# 780-00012-P1_Sch_M2_Focus_Drive.net
KiCad netlist of a schematic drawn in Altium Designer
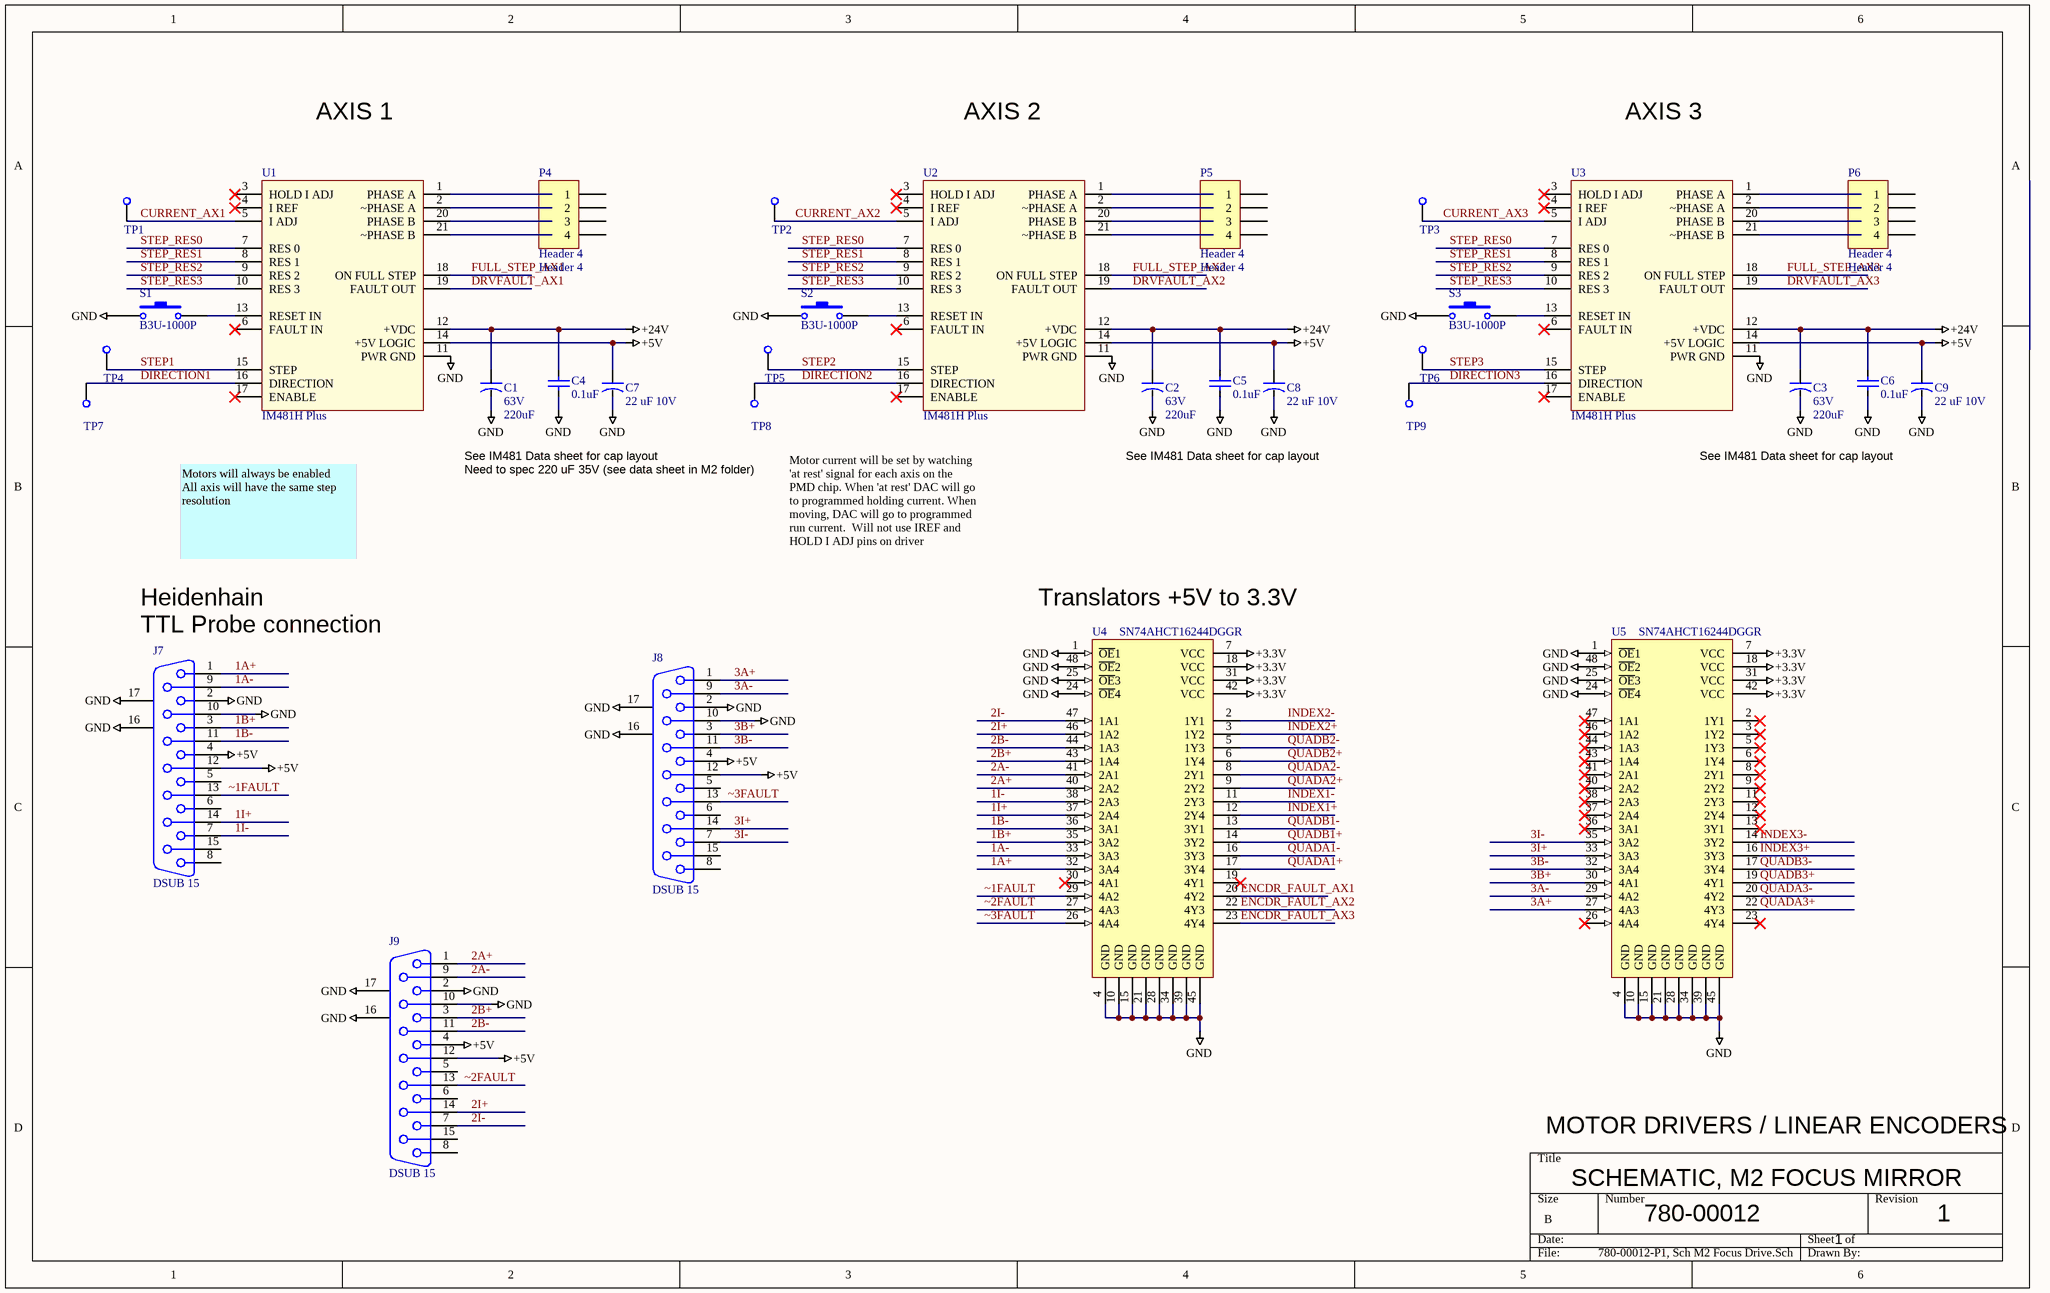
[diagram p0: 780-00012-P1, Sch M2 Focus Drive.SchDoc]

(export (version "E")
  (design (tool "Eeschema 10.0.6"))
  (components
    (comp (ref "C1")
      (value "63V")
      (footprint "CAP 220uF 63V")
      (description "CAP 220UF 63V ELECT MVH SMD")
      (fields (field (name "MANUFACTURER") "United Chemi-Con") (field (name "ALTIUM_VALUE") "220uF"))
      (libsource (lib "Richs Schematic Components") (part "Cap 220uF, 63V"))
    )
    (comp (ref "C2")
      (value "63V")
      (footprint "CAP 220uF 63V")
      (description "CAP 220UF 63V ELECT MVH SMD")
      (fields (field (name "MANUFACTURER") "United Chemi-Con") (field (name "ALTIUM_VALUE") "220uF"))
      (libsource (lib "Richs Schematic Components") (part "Cap 220uF, 63V"))
    )
    (comp (ref "C3")
      (value "63V")
      (footprint "CAP 220uF 63V")
      (description "CAP 220UF 63V ELECT MVH SMD")
      (fields (field (name "MANUFACTURER") "United Chemi-Con") (field (name "ALTIUM_VALUE") "220uF"))
      (libsource (lib "Richs Schematic Components") (part "Cap 220uF, 63V"))
    )
    (comp (ref "C4")
      (value "0.1uF")
      (footprint "SMD_0805")
      (description "Capacitor")
      (fields (field (name "Comment") "Cap SMD"))
      (libsource (lib "Richs Schematic Components") (part "Cap SMD"))
    )
    (comp (ref "C5")
      (value "0.1uF")
      (footprint "SMD_0805")
      (description "Capacitor")
      (fields (field (name "Comment") "Cap SMD"))
      (libsource (lib "Richs Schematic Components") (part "Cap SMD"))
    )
    (comp (ref "C6")
      (value "0.1uF")
      (footprint "SMD_0805")
      (description "Capacitor")
      (fields (field (name "Comment") "Cap SMD"))
      (libsource (lib "Richs Schematic Components") (part "Cap SMD"))
    )
    (comp (ref "C7")
      (value "22 uF 10V")
      (footprint "SMD_CAP_3216")
      (description "outline 3.2mm x 1.6mm")
      (fields (field (name "MANUFACTURER") "KEMET") (field (name "Comment") "16V"))
      (libsource (lib "Richs Schematic Components") (part "Cap Tant 16V"))
    )
    (comp (ref "C8")
      (value "22 uF 10V")
      (footprint "SMD_CAP_3216")
      (description "outline 3.2mm x 1.6mm")
      (fields (field (name "MANUFACTURER") "KEMET") (field (name "Comment") "16V"))
      (libsource (lib "Richs Schematic Components") (part "Cap Tant 16V"))
    )
    (comp (ref "C9")
      (value "22 uF 10V")
      (footprint "SMD_CAP_3216")
      (description "outline 3.2mm x 1.6mm")
      (fields (field (name "MANUFACTURER") "KEMET") (field (name "Comment") "16V"))
      (libsource (lib "Richs Schematic Components") (part "Cap Tant 16V"))
    )
    (comp (ref "J7")
      (value "DSUB 15")
      (footprint "DSUB15 PCB VERT Female")
      (description "Receptacle Assembly, 15 Position")
      (libsource (lib "Richs Schematic Components") (part "DSUB 15"))
    )
    (comp (ref "J8")
      (value "DSUB 15")
      (footprint "DSUB15 PCB VERT Female")
      (description "Receptacle Assembly, 15 Position")
      (libsource (lib "Richs Schematic Components") (part "DSUB 15"))
    )
    (comp (ref "J9")
      (value "DSUB 15")
      (footprint "DSUB15 PCB VERT Female")
      (description "Receptacle Assembly, 15 Position")
      (libsource (lib "Richs Schematic Components") (part "DSUB 15"))
    )
    (comp (ref "P4")
      (value "Header 4")
      (footprint "HDR1X4 for IDC")
      (description "Header, 4-Pin")
      (fields (field (name "ALTIUM_VALUE") "Header 4"))
      (libsource (lib "Richs Schematic Components") (part "Header 4"))
    )
    (comp (ref "P5")
      (value "Header 4")
      (footprint "HDR1X4 for IDC")
      (description "Header, 4-Pin")
      (fields (field (name "ALTIUM_VALUE") "Header 4"))
      (libsource (lib "Richs Schematic Components") (part "Header 4"))
    )
    (comp (ref "P6")
      (value "Header 4")
      (footprint "HDR1X4 for IDC")
      (description "Header, 4-Pin")
      (fields (field (name "ALTIUM_VALUE") "Header 4"))
      (libsource (lib "Richs Schematic Components") (part "Header 4"))
    )
    (comp (ref "S1")
      (value "B3U-1000P")
      (footprint "B3U-1000P")
      (description "Switch")
      (fields (field (name "MANUFACTURER") "Omron Electronics"))
      (libsource (lib "Miscellaneous Devices") (part "SW-PB"))
    )
    (comp (ref "S2")
      (value "B3U-1000P")
      (footprint "B3U-1000P")
      (description "Switch")
      (fields (field (name "MANUFACTURER") "Omron Electronics"))
      (libsource (lib "Miscellaneous Devices") (part "SW-PB"))
    )
    (comp (ref "S3")
      (value "B3U-1000P")
      (footprint "B3U-1000P")
      (description "Switch")
      (fields (field (name "MANUFACTURER") "Omron Electronics"))
      (libsource (lib "Miscellaneous Devices") (part "SW-PB"))
    )
    (comp (ref "TP1")
      (value "Test Point SMD")
      (footprint "SMD_TEST POINT")
      (description "SMD loop test point")
      (libsource (lib "Richs Schematic Components") (part "Test Point SMD"))
    )
    (comp (ref "TP2")
      (value "Test Point SMD")
      (footprint "SMD_TEST POINT")
      (description "SMD loop test point")
      (libsource (lib "Richs Schematic Components") (part "Test Point SMD"))
    )
    (comp (ref "TP3")
      (value "Test Point SMD")
      (footprint "SMD_TEST POINT")
      (description "SMD loop test point")
      (libsource (lib "Richs Schematic Components") (part "Test Point SMD"))
    )
    (comp (ref "TP4")
      (value "Test Point SMD")
      (footprint "SMD_TEST POINT")
      (description "SMD loop test point")
      (libsource (lib "Richs Schematic Components") (part "Test Point SMD"))
    )
    (comp (ref "TP5")
      (value "Test Point SMD")
      (footprint "SMD_TEST POINT")
      (description "SMD loop test point")
      (libsource (lib "Richs Schematic Components") (part "Test Point SMD"))
    )
    (comp (ref "TP6")
      (value "Test Point SMD")
      (footprint "SMD_TEST POINT")
      (description "SMD loop test point")
      (libsource (lib "Richs Schematic Components") (part "Test Point SMD"))
    )
    (comp (ref "TP7")
      (value "Test Point SMD")
      (footprint "SMD_TEST POINT")
      (description "SMD loop test point")
      (libsource (lib "Richs Schematic Components") (part "Test Point SMD"))
    )
    (comp (ref "TP8")
      (value "Test Point SMD")
      (footprint "SMD_TEST POINT")
      (description "SMD loop test point")
      (libsource (lib "Richs Schematic Components") (part "Test Point SMD"))
    )
    (comp (ref "TP9")
      (value "Test Point SMD")
      (footprint "SMD_TEST POINT")
      (description "SMD loop test point")
      (libsource (lib "Richs Schematic Components") (part "Test Point SMD"))
    )
    (comp (ref "U1")
      (value "IM481H Plus")
      (footprint "IM481H Vertical")
      (description "Hybrid stepper motor driver")
      (libsource (lib "Richs Schematic Components") (part "IM481H Plus"))
    )
    (comp (ref "U2")
      (value "IM481H Plus")
      (footprint "IM481H Vertical")
      (description "Hybrid stepper motor driver")
      (libsource (lib "Richs Schematic Components") (part "IM481H Plus"))
    )
    (comp (ref "U3")
      (value "IM481H Plus")
      (footprint "IM481H Vertical")
      (description "Hybrid stepper motor driver")
      (libsource (lib "Richs Schematic Components") (part "IM481H Plus"))
    )
    (comp (ref "U4")
      (value "SN74AHCT16244DGGR")
      (footprint "DGG048_N")
      (description "16-Bit Buffer/Driver with 3-State Outputs")
      (libsource (lib "TI Logic Buffer Line Driver") (part "SN74AHCT16244DGGR"))
    )
    (comp (ref "U5")
      (value "SN74AHCT16244DGGR")
      (footprint "DGG048_N")
      (description "16-Bit Buffer/Driver with 3-State Outputs")
      (libsource (lib "TI Logic Buffer Line Driver") (part "SN74AHCT16244DGGR"))
    )
  )
  (nets
    (net (code "1") (name "+3.3V") (class "Default")
      (node (ref "U4") (pin "18") (pinfunction "VCC_18") (pintype "power_in"))
      (node (ref "U4") (pin "31") (pinfunction "VCC_31") (pintype "power_in"))
      (node (ref "U4") (pin "42") (pinfunction "VCC_42") (pintype "power_in"))
      (node (ref "U4") (pin "7") (pinfunction "VCC_7") (pintype "power_in"))
      (node (ref "U5") (pin "18") (pinfunction "VCC_18") (pintype "power_in"))
      (node (ref "U5") (pin "31") (pinfunction "VCC_31") (pintype "power_in"))
      (node (ref "U5") (pin "42") (pinfunction "VCC_42") (pintype "power_in"))
      (node (ref "U5") (pin "7") (pinfunction "VCC_7") (pintype "power_in"))
    )
    (net (code "2") (name "+5V") (class "Default")
      (node (ref "C7") (pin "1") (pinfunction "1_1") (pintype "passive"))
      (node (ref "C8") (pin "1") (pinfunction "1_1") (pintype "passive"))
      (node (ref "C9") (pin "1") (pinfunction "1_1") (pintype "passive"))
      (node (ref "J7") (pin "12") (pinfunction "12_12") (pintype "passive"))
      (node (ref "J7") (pin "4") (pinfunction "4_4") (pintype "passive"))
      (node (ref "J8") (pin "12") (pinfunction "12_12") (pintype "passive"))
      (node (ref "J8") (pin "4") (pinfunction "4_4") (pintype "passive"))
      (node (ref "J9") (pin "12") (pinfunction "12_12") (pintype "passive"))
      (node (ref "J9") (pin "4") (pinfunction "4_4") (pintype "passive"))
      (node (ref "U1") (pin "14") (pinfunction "+5V_LOGIC_14") (pintype "passive"))
      (node (ref "U2") (pin "14") (pinfunction "+5V_LOGIC_14") (pintype "passive"))
      (node (ref "U3") (pin "14") (pinfunction "+5V_LOGIC_14") (pintype "passive"))
    )
    (net (code "3") (name "+24V") (class "Default")
      (node (ref "C1") (pin "1") (pinfunction "1_1") (pintype "passive"))
      (node (ref "C2") (pin "1") (pinfunction "1_1") (pintype "passive"))
      (node (ref "C3") (pin "1") (pinfunction "1_1") (pintype "passive"))
      (node (ref "C4") (pin "2") (pinfunction "2_2") (pintype "passive"))
      (node (ref "C5") (pin "2") (pinfunction "2_2") (pintype "passive"))
      (node (ref "C6") (pin "2") (pinfunction "2_2") (pintype "passive"))
      (node (ref "U1") (pin "12") (pinfunction "+VDC_12") (pintype "passive"))
      (node (ref "U2") (pin "12") (pinfunction "+VDC_12") (pintype "passive"))
      (node (ref "U3") (pin "12") (pinfunction "+VDC_12") (pintype "passive"))
    )
    (net (code "4") (name "/1A+") (class "Default")
      (node (ref "J7") (pin "1") (pinfunction "1_1") (pintype "passive"))
      (node (ref "U4") (pin "32") (pinfunction "3A4_32") (pintype "input"))
    )
    (net (code "5") (name "/1A-") (class "Default")
      (node (ref "J7") (pin "9") (pinfunction "9_9") (pintype "passive"))
      (node (ref "U4") (pin "33") (pinfunction "3A3_33") (pintype "input"))
    )
    (net (code "6") (name "/1B+") (class "Default")
      (node (ref "J7") (pin "3") (pinfunction "3_3") (pintype "passive"))
      (node (ref "U4") (pin "35") (pinfunction "3A2_35") (pintype "input"))
    )
    (net (code "7") (name "/1B-") (class "Default")
      (node (ref "J7") (pin "11") (pinfunction "11_11") (pintype "passive"))
      (node (ref "U4") (pin "36") (pinfunction "3A1_36") (pintype "input"))
    )
    (net (code "8") (name "/1I+") (class "Default")
      (node (ref "J7") (pin "14") (pinfunction "14_14") (pintype "passive"))
      (node (ref "U4") (pin "37") (pinfunction "2A4_37") (pintype "input"))
    )
    (net (code "9") (name "/1I-") (class "Default")
      (node (ref "J7") (pin "7") (pinfunction "7_7") (pintype "passive"))
      (node (ref "U4") (pin "38") (pinfunction "2A3_38") (pintype "input"))
    )
    (net (code "10") (name "/2A+") (class "Default")
      (node (ref "J9") (pin "1") (pinfunction "1_1") (pintype "passive"))
      (node (ref "U4") (pin "40") (pinfunction "2A2_40") (pintype "input"))
    )
    (net (code "11") (name "/2A-") (class "Default")
      (node (ref "J9") (pin "9") (pinfunction "9_9") (pintype "passive"))
      (node (ref "U4") (pin "41") (pinfunction "2A1_41") (pintype "input"))
    )
    (net (code "12") (name "/2B+") (class "Default")
      (node (ref "J9") (pin "3") (pinfunction "3_3") (pintype "passive"))
      (node (ref "U4") (pin "43") (pinfunction "1A4_43") (pintype "input"))
    )
    (net (code "13") (name "/2B-") (class "Default")
      (node (ref "J9") (pin "11") (pinfunction "11_11") (pintype "passive"))
      (node (ref "U4") (pin "44") (pinfunction "1A3_44") (pintype "input"))
    )
    (net (code "14") (name "/2I+") (class "Default")
      (node (ref "J9") (pin "14") (pinfunction "14_14") (pintype "passive"))
      (node (ref "U4") (pin "46") (pinfunction "1A2_46") (pintype "input"))
    )
    (net (code "15") (name "/2I-") (class "Default")
      (node (ref "J9") (pin "7") (pinfunction "7_7") (pintype "passive"))
      (node (ref "U4") (pin "47") (pinfunction "1A1_47") (pintype "input"))
    )
    (net (code "16") (name "/3A+") (class "Default")
      (node (ref "J8") (pin "1") (pinfunction "1_1") (pintype "passive"))
      (node (ref "U5") (pin "27") (pinfunction "4A3_27") (pintype "input"))
    )
    (net (code "17") (name "/3A-") (class "Default")
      (node (ref "J8") (pin "9") (pinfunction "9_9") (pintype "passive"))
      (node (ref "U5") (pin "29") (pinfunction "4A2_29") (pintype "input"))
    )
    (net (code "18") (name "/3B+") (class "Default")
      (node (ref "J8") (pin "3") (pinfunction "3_3") (pintype "passive"))
      (node (ref "U5") (pin "30") (pinfunction "4A1_30") (pintype "input"))
    )
    (net (code "19") (name "/3B-") (class "Default")
      (node (ref "J8") (pin "11") (pinfunction "11_11") (pintype "passive"))
      (node (ref "U5") (pin "32") (pinfunction "3A4_32") (pintype "input"))
    )
    (net (code "20") (name "/3I+") (class "Default")
      (node (ref "J8") (pin "14") (pinfunction "14_14") (pintype "passive"))
      (node (ref "U5") (pin "33") (pinfunction "3A3_33") (pintype "input"))
    )
    (net (code "21") (name "/3I-") (class "Default")
      (node (ref "J8") (pin "7") (pinfunction "7_7") (pintype "passive"))
      (node (ref "U5") (pin "35") (pinfunction "3A2_35") (pintype "input"))
    )
    (net (code "22") (name "/CURRENT_AX1") (class "Default")
      (node (ref "TP1") (pin "1") (pinfunction "TP_1") (pintype "passive"))
      (node (ref "U1") (pin "5") (pinfunction "I_ADJ_5") (pintype "passive"))
    )
    (net (code "23") (name "/CURRENT_AX2") (class "Default")
      (node (ref "TP2") (pin "1") (pinfunction "TP_1") (pintype "passive"))
      (node (ref "U2") (pin "5") (pinfunction "I_ADJ_5") (pintype "passive"))
    )
    (net (code "24") (name "/CURRENT_AX3") (class "Default")
      (node (ref "TP3") (pin "1") (pinfunction "TP_1") (pintype "passive"))
      (node (ref "U3") (pin "5") (pinfunction "I_ADJ_5") (pintype "passive"))
    )
    (net (code "25") (name "/DIRECTION1") (class "Default")
      (node (ref "TP7") (pin "1") (pinfunction "TP_1") (pintype "passive"))
      (node (ref "U1") (pin "16") (pinfunction "DIRECTION_16") (pintype "passive"))
    )
    (net (code "26") (name "/DIRECTION2") (class "Default")
      (node (ref "TP8") (pin "1") (pinfunction "TP_1") (pintype "passive"))
      (node (ref "U2") (pin "16") (pinfunction "DIRECTION_16") (pintype "passive"))
    )
    (net (code "27") (name "/DIRECTION3") (class "Default")
      (node (ref "TP9") (pin "1") (pinfunction "TP_1") (pintype "passive"))
      (node (ref "U3") (pin "16") (pinfunction "DIRECTION_16") (pintype "passive"))
    )
    (net (code "28") (name "/DRVFAULT_AX1") (class "Default")
      (node (ref "U1") (pin "19") (pinfunction "FAULT_OUT_19") (pintype "passive"))
    )
    (net (code "29") (name "/DRVFAULT_AX2") (class "Default")
      (node (ref "U2") (pin "19") (pinfunction "FAULT_OUT_19") (pintype "passive"))
    )
    (net (code "30") (name "/DRVFAULT_AX3") (class "Default")
      (node (ref "U3") (pin "19") (pinfunction "FAULT_OUT_19") (pintype "passive"))
    )
    (net (code "31") (name "/ENCDR_FAULT_AX1") (class "Default")
      (node (ref "U4") (pin "20") (pinfunction "4Y2_20") (pintype "tri_state"))
    )
    (net (code "32") (name "/ENCDR_FAULT_AX2") (class "Default")
      (node (ref "U4") (pin "22") (pinfunction "4Y3_22") (pintype "tri_state"))
    )
    (net (code "33") (name "/ENCDR_FAULT_AX3") (class "Default")
      (node (ref "U4") (pin "23") (pinfunction "4Y4_23") (pintype "tri_state"))
    )
    (net (code "34") (name "/FULL_STEP_AX1") (class "Default")
      (node (ref "U1") (pin "18") (pinfunction "ON_FULL_STEP_18") (pintype "passive"))
    )
    (net (code "35") (name "/FULL_STEP_AX2") (class "Default")
      (node (ref "U2") (pin "18") (pinfunction "ON_FULL_STEP_18") (pintype "passive"))
    )
    (net (code "36") (name "/FULL_STEP_AX3") (class "Default")
      (node (ref "U3") (pin "18") (pinfunction "ON_FULL_STEP_18") (pintype "passive"))
    )
    (net (code "37") (name "/INDEX1+") (class "Default")
      (node (ref "U4") (pin "12") (pinfunction "2Y4_12") (pintype "tri_state"))
    )
    (net (code "38") (name "/INDEX1-") (class "Default")
      (node (ref "U4") (pin "11") (pinfunction "2Y3_11") (pintype "tri_state"))
    )
    (net (code "39") (name "/INDEX2+") (class "Default")
      (node (ref "U4") (pin "3") (pinfunction "1Y2_3") (pintype "tri_state"))
    )
    (net (code "40") (name "/INDEX2-") (class "Default")
      (node (ref "U4") (pin "2") (pinfunction "1Y1_2") (pintype "tri_state"))
    )
    (net (code "41") (name "/INDEX3+") (class "Default")
      (node (ref "U5") (pin "16") (pinfunction "3Y3_16") (pintype "tri_state"))
    )
    (net (code "42") (name "/INDEX3-") (class "Default")
      (node (ref "U5") (pin "14") (pinfunction "3Y2_14") (pintype "tri_state"))
    )
    (net (code "43") (name "/QUADA1+") (class "Default")
      (node (ref "U4") (pin "17") (pinfunction "3Y4_17") (pintype "tri_state"))
    )
    (net (code "44") (name "/QUADA1-") (class "Default")
      (node (ref "U4") (pin "16") (pinfunction "3Y3_16") (pintype "tri_state"))
    )
    (net (code "45") (name "/QUADA2+") (class "Default")
      (node (ref "U4") (pin "9") (pinfunction "2Y2_9") (pintype "tri_state"))
    )
    (net (code "46") (name "/QUADA2-") (class "Default")
      (node (ref "U4") (pin "8") (pinfunction "2Y1_8") (pintype "tri_state"))
    )
    (net (code "47") (name "/QUADA3+") (class "Default")
      (node (ref "U5") (pin "22") (pinfunction "4Y3_22") (pintype "tri_state"))
    )
    (net (code "48") (name "/QUADA3-") (class "Default")
      (node (ref "U5") (pin "20") (pinfunction "4Y2_20") (pintype "tri_state"))
    )
    (net (code "49") (name "/QUADB1+") (class "Default")
      (node (ref "U4") (pin "14") (pinfunction "3Y2_14") (pintype "tri_state"))
    )
    (net (code "50") (name "/QUADB1-") (class "Default")
      (node (ref "U4") (pin "13") (pinfunction "3Y1_13") (pintype "tri_state"))
    )
    (net (code "51") (name "/QUADB2+") (class "Default")
      (node (ref "U4") (pin "6") (pinfunction "1Y4_6") (pintype "tri_state"))
    )
    (net (code "52") (name "/QUADB2-") (class "Default")
      (node (ref "U4") (pin "5") (pinfunction "1Y3_5") (pintype "tri_state"))
    )
    (net (code "53") (name "/QUADB3+") (class "Default")
      (node (ref "U5") (pin "19") (pinfunction "4Y1_19") (pintype "tri_state"))
    )
    (net (code "54") (name "/QUADB3-") (class "Default")
      (node (ref "U5") (pin "17") (pinfunction "3Y4_17") (pintype "tri_state"))
    )
    (net (code "55") (name "/STEP1") (class "Default")
      (node (ref "TP4") (pin "1") (pinfunction "TP_1") (pintype "passive"))
      (node (ref "U1") (pin "15") (pinfunction "STEP_15") (pintype "passive"))
    )
    (net (code "56") (name "/STEP2") (class "Default")
      (node (ref "TP5") (pin "1") (pinfunction "TP_1") (pintype "passive"))
      (node (ref "U2") (pin "15") (pinfunction "STEP_15") (pintype "passive"))
    )
    (net (code "57") (name "/STEP3") (class "Default")
      (node (ref "TP6") (pin "1") (pinfunction "TP_1") (pintype "passive"))
      (node (ref "U3") (pin "15") (pinfunction "STEP_15") (pintype "passive"))
    )
    (net (code "58") (name "/STEP_RES0") (class "Default")
      (node (ref "U1") (pin "7") (pinfunction "RES_0_7") (pintype "passive"))
      (node (ref "U2") (pin "7") (pinfunction "RES_0_7") (pintype "passive"))
      (node (ref "U3") (pin "7") (pinfunction "RES_0_7") (pintype "passive"))
    )
    (net (code "59") (name "/STEP_RES1") (class "Default")
      (node (ref "U1") (pin "8") (pinfunction "RES_1_8") (pintype "passive"))
      (node (ref "U2") (pin "8") (pinfunction "RES_1_8") (pintype "passive"))
      (node (ref "U3") (pin "8") (pinfunction "RES_1_8") (pintype "passive"))
    )
    (net (code "60") (name "/STEP_RES2") (class "Default")
      (node (ref "U1") (pin "9") (pinfunction "RES_2_9") (pintype "passive"))
      (node (ref "U2") (pin "9") (pinfunction "RES_2_9") (pintype "passive"))
      (node (ref "U3") (pin "9") (pinfunction "RES_2_9") (pintype "passive"))
    )
    (net (code "61") (name "/STEP_RES3") (class "Default")
      (node (ref "U1") (pin "10") (pinfunction "RES_3_10") (pintype "passive"))
      (node (ref "U2") (pin "10") (pinfunction "RES_3_10") (pintype "passive"))
      (node (ref "U3") (pin "10") (pinfunction "RES_3_10") (pintype "passive"))
    )
    (net (code "62") (name "/~1FAULT") (class "Default")
      (node (ref "J7") (pin "13") (pinfunction "13_13") (pintype "passive"))
      (node (ref "U4") (pin "29") (pinfunction "4A2_29") (pintype "input"))
    )
    (net (code "63") (name "/~2FAULT") (class "Default")
      (node (ref "J9") (pin "13") (pinfunction "13_13") (pintype "passive"))
      (node (ref "U4") (pin "27") (pinfunction "4A3_27") (pintype "input"))
    )
    (net (code "64") (name "/~3FAULT") (class "Default")
      (node (ref "J8") (pin "13") (pinfunction "13_13") (pintype "passive"))
      (node (ref "U4") (pin "26") (pinfunction "4A4_26") (pintype "input"))
    )
    (net (code "65") (name "GND") (class "Default")
      (node (ref "C1") (pin "2") (pinfunction "2_2") (pintype "passive"))
      (node (ref "C2") (pin "2") (pinfunction "2_2") (pintype "passive"))
      (node (ref "C3") (pin "2") (pinfunction "2_2") (pintype "passive"))
      (node (ref "C4") (pin "1") (pinfunction "1_1") (pintype "passive"))
      (node (ref "C5") (pin "1") (pinfunction "1_1") (pintype "passive"))
      (node (ref "C6") (pin "1") (pinfunction "1_1") (pintype "passive"))
      (node (ref "C7") (pin "2") (pinfunction "2_2") (pintype "passive"))
      (node (ref "C8") (pin "2") (pinfunction "2_2") (pintype "passive"))
      (node (ref "C9") (pin "2") (pinfunction "2_2") (pintype "passive"))
      (node (ref "J7") (pin "10") (pinfunction "10_10") (pintype "passive"))
      (node (ref "J7") (pin "16") (pinfunction "MH1_16") (pintype "passive"))
      (node (ref "J7") (pin "17") (pinfunction "MH2_17") (pintype "passive"))
      (node (ref "J7") (pin "2") (pinfunction "2_2") (pintype "passive"))
      (node (ref "J8") (pin "10") (pinfunction "10_10") (pintype "passive"))
      (node (ref "J8") (pin "16") (pinfunction "MH1_16") (pintype "passive"))
      (node (ref "J8") (pin "17") (pinfunction "MH2_17") (pintype "passive"))
      (node (ref "J8") (pin "2") (pinfunction "2_2") (pintype "passive"))
      (node (ref "J9") (pin "10") (pinfunction "10_10") (pintype "passive"))
      (node (ref "J9") (pin "16") (pinfunction "MH1_16") (pintype "passive"))
      (node (ref "J9") (pin "17") (pinfunction "MH2_17") (pintype "passive"))
      (node (ref "J9") (pin "2") (pinfunction "2_2") (pintype "passive"))
      (node (ref "S1") (pin "1") (pinfunction "1_1") (pintype "passive"))
      (node (ref "S2") (pin "1") (pinfunction "1_1") (pintype "passive"))
      (node (ref "S3") (pin "1") (pinfunction "1_1") (pintype "passive"))
      (node (ref "U1") (pin "11") (pinfunction "PWR_GND_11") (pintype "passive"))
      (node (ref "U2") (pin "11") (pinfunction "PWR_GND_11") (pintype "passive"))
      (node (ref "U3") (pin "11") (pinfunction "PWR_GND_11") (pintype "passive"))
      (node (ref "U4") (pin "1") (pinfunction "~{OE}1_1") (pintype "input"))
      (node (ref "U4") (pin "10") (pinfunction "GND_10") (pintype "power_in"))
      (node (ref "U4") (pin "15") (pinfunction "GND_15") (pintype "power_in"))
      (node (ref "U4") (pin "21") (pinfunction "GND_21") (pintype "power_in"))
      (node (ref "U4") (pin "24") (pinfunction "~{OE}4_24") (pintype "input"))
      (node (ref "U4") (pin "25") (pinfunction "~{OE}3_25") (pintype "input"))
      (node (ref "U4") (pin "28") (pinfunction "GND_28") (pintype "power_in"))
      (node (ref "U4") (pin "34") (pinfunction "GND_34") (pintype "power_in"))
      (node (ref "U4") (pin "39") (pinfunction "GND_39") (pintype "power_in"))
      (node (ref "U4") (pin "4") (pinfunction "GND_4") (pintype "power_in"))
      (node (ref "U4") (pin "45") (pinfunction "GND_45") (pintype "power_in"))
      (node (ref "U4") (pin "48") (pinfunction "~{OE}2_48") (pintype "input"))
      (node (ref "U5") (pin "1") (pinfunction "~{OE}1_1") (pintype "input"))
      (node (ref "U5") (pin "10") (pinfunction "GND_10") (pintype "power_in"))
      (node (ref "U5") (pin "15") (pinfunction "GND_15") (pintype "power_in"))
      (node (ref "U5") (pin "21") (pinfunction "GND_21") (pintype "power_in"))
      (node (ref "U5") (pin "24") (pinfunction "~{OE}4_24") (pintype "input"))
      (node (ref "U5") (pin "25") (pinfunction "~{OE}3_25") (pintype "input"))
      (node (ref "U5") (pin "28") (pinfunction "GND_28") (pintype "power_in"))
      (node (ref "U5") (pin "34") (pinfunction "GND_34") (pintype "power_in"))
      (node (ref "U5") (pin "39") (pinfunction "GND_39") (pintype "power_in"))
      (node (ref "U5") (pin "4") (pinfunction "GND_4") (pintype "power_in"))
      (node (ref "U5") (pin "45") (pinfunction "GND_45") (pintype "power_in"))
      (node (ref "U5") (pin "48") (pinfunction "~{OE}2_48") (pintype "input"))
    )
    (net (code "66") (name "Net-(U1-RESET_IN)") (class "Default")
      (node (ref "S1") (pin "2") (pinfunction "2_2") (pintype "passive"))
      (node (ref "U1") (pin "13") (pinfunction "RESET_IN_13") (pintype "passive"))
    )
    (net (code "67") (name "Net-(U2-RESET_IN)") (class "Default")
      (node (ref "S2") (pin "2") (pinfunction "2_2") (pintype "passive"))
      (node (ref "U2") (pin "13") (pinfunction "RESET_IN_13") (pintype "passive"))
    )
    (net (code "68") (name "Net-(U3-RESET_IN)") (class "Default")
      (node (ref "S3") (pin "2") (pinfunction "2_2") (pintype "passive"))
      (node (ref "U3") (pin "13") (pinfunction "RESET_IN_13") (pintype "passive"))
    )
    (net (code "69") (name "unconnected-(J7-Pad5)") (class "Default")
      (node (ref "J7") (pin "5") (pinfunction "5_5") (pintype "passive"))
    )
    (net (code "70") (name "unconnected-(J7-Pad6)") (class "Default")
      (node (ref "J7") (pin "6") (pinfunction "6_6") (pintype "passive"))
    )
    (net (code "71") (name "unconnected-(J7-Pad8)") (class "Default")
      (node (ref "J7") (pin "8") (pinfunction "8_8") (pintype "passive"))
    )
    (net (code "72") (name "unconnected-(J7-Pad15)") (class "Default")
      (node (ref "J7") (pin "15") (pinfunction "15_15") (pintype "passive"))
    )
    (net (code "73") (name "unconnected-(J8-Pad5)") (class "Default")
      (node (ref "J8") (pin "5") (pinfunction "5_5") (pintype "passive"))
    )
    (net (code "74") (name "unconnected-(J8-Pad6)") (class "Default")
      (node (ref "J8") (pin "6") (pinfunction "6_6") (pintype "passive"))
    )
    (net (code "75") (name "unconnected-(J8-Pad8)") (class "Default")
      (node (ref "J8") (pin "8") (pinfunction "8_8") (pintype "passive"))
    )
    (net (code "76") (name "unconnected-(J8-Pad15)") (class "Default")
      (node (ref "J8") (pin "15") (pinfunction "15_15") (pintype "passive"))
    )
    (net (code "77") (name "unconnected-(J9-Pad5)") (class "Default")
      (node (ref "J9") (pin "5") (pinfunction "5_5") (pintype "passive"))
    )
    (net (code "78") (name "unconnected-(J9-Pad6)") (class "Default")
      (node (ref "J9") (pin "6") (pinfunction "6_6") (pintype "passive"))
    )
    (net (code "79") (name "unconnected-(J9-Pad8)") (class "Default")
      (node (ref "J9") (pin "8") (pinfunction "8_8") (pintype "passive"))
    )
    (net (code "80") (name "unconnected-(J9-Pad15)") (class "Default")
      (node (ref "J9") (pin "15") (pinfunction "15_15") (pintype "passive"))
    )
    (net (code "81") (name "unconnected-(P4-Pad1)") (class "Default")
      (node (ref "P4") (pin "1") (pinfunction "1_1") (pintype "passive"))
    )
    (net (code "82") (name "unconnected-(P4-Pad2)") (class "Default")
      (node (ref "P4") (pin "2") (pinfunction "2_2") (pintype "passive"))
    )
    (net (code "83") (name "unconnected-(P4-Pad3)") (class "Default")
      (node (ref "P4") (pin "3") (pinfunction "3_3") (pintype "passive"))
    )
    (net (code "84") (name "unconnected-(P4-Pad4)") (class "Default")
      (node (ref "P4") (pin "4") (pinfunction "4_4") (pintype "passive"))
    )
    (net (code "85") (name "unconnected-(P5-Pad1)") (class "Default")
      (node (ref "P5") (pin "1") (pinfunction "1_1") (pintype "passive"))
    )
    (net (code "86") (name "unconnected-(P5-Pad2)") (class "Default")
      (node (ref "P5") (pin "2") (pinfunction "2_2") (pintype "passive"))
    )
    (net (code "87") (name "unconnected-(P5-Pad3)") (class "Default")
      (node (ref "P5") (pin "3") (pinfunction "3_3") (pintype "passive"))
    )
    (net (code "88") (name "unconnected-(P5-Pad4)") (class "Default")
      (node (ref "P5") (pin "4") (pinfunction "4_4") (pintype "passive"))
    )
    (net (code "89") (name "unconnected-(P6-Pad1)") (class "Default")
      (node (ref "P6") (pin "1") (pinfunction "1_1") (pintype "passive"))
    )
    (net (code "90") (name "unconnected-(P6-Pad2)") (class "Default")
      (node (ref "P6") (pin "2") (pinfunction "2_2") (pintype "passive"))
    )
    (net (code "91") (name "unconnected-(P6-Pad3)") (class "Default")
      (node (ref "P6") (pin "3") (pinfunction "3_3") (pintype "passive"))
    )
    (net (code "92") (name "unconnected-(P6-Pad4)") (class "Default")
      (node (ref "P6") (pin "4") (pinfunction "4_4") (pintype "passive"))
    )
    (net (code "93") (name "unconnected-(U1-ENABLE-Pad17)") (class "Default")
      (node (ref "U1") (pin "17") (pinfunction "ENABLE_17") (pintype "passive+no_connect"))
    )
    (net (code "94") (name "unconnected-(U1-FAULT_IN-Pad6)") (class "Default")
      (node (ref "U1") (pin "6") (pinfunction "FAULT_IN_6") (pintype "passive+no_connect"))
    )
    (net (code "95") (name "unconnected-(U1-HOLD_I_ADJ-Pad3)") (class "Default")
      (node (ref "U1") (pin "3") (pinfunction "HOLD_I_ADJ_3") (pintype "passive+no_connect"))
    )
    (net (code "96") (name "unconnected-(U1-I_REF-Pad4)") (class "Default")
      (node (ref "U1") (pin "4") (pinfunction "I_REF_4") (pintype "passive+no_connect"))
    )
    (net (code "97") (name "unconnected-(U1-PHASE_A-Pad1)") (class "Default")
      (node (ref "U1") (pin "1") (pinfunction "PHASE_A_1") (pintype "passive"))
    )
    (net (code "98") (name "unconnected-(U1-PHASE_B-Pad20)") (class "Default")
      (node (ref "U1") (pin "20") (pinfunction "PHASE_B_20") (pintype "passive"))
    )
    (net (code "99") (name "unconnected-(U1-~PHASE_A-Pad2)") (class "Default")
      (node (ref "U1") (pin "2") (pinfunction "~PHASE_A_2") (pintype "passive"))
    )
    (net (code "100") (name "unconnected-(U1-~PHASE_B-Pad21)") (class "Default")
      (node (ref "U1") (pin "21") (pinfunction "~PHASE_B_21") (pintype "passive"))
    )
    (net (code "101") (name "unconnected-(U2-ENABLE-Pad17)") (class "Default")
      (node (ref "U2") (pin "17") (pinfunction "ENABLE_17") (pintype "passive+no_connect"))
    )
    (net (code "102") (name "unconnected-(U2-FAULT_IN-Pad6)") (class "Default")
      (node (ref "U2") (pin "6") (pinfunction "FAULT_IN_6") (pintype "passive+no_connect"))
    )
    (net (code "103") (name "unconnected-(U2-HOLD_I_ADJ-Pad3)") (class "Default")
      (node (ref "U2") (pin "3") (pinfunction "HOLD_I_ADJ_3") (pintype "passive+no_connect"))
    )
    (net (code "104") (name "unconnected-(U2-I_REF-Pad4)") (class "Default")
      (node (ref "U2") (pin "4") (pinfunction "I_REF_4") (pintype "passive+no_connect"))
    )
    (net (code "105") (name "unconnected-(U2-PHASE_A-Pad1)") (class "Default")
      (node (ref "U2") (pin "1") (pinfunction "PHASE_A_1") (pintype "passive"))
    )
    (net (code "106") (name "unconnected-(U2-PHASE_B-Pad20)") (class "Default")
      (node (ref "U2") (pin "20") (pinfunction "PHASE_B_20") (pintype "passive"))
    )
    (net (code "107") (name "unconnected-(U2-~PHASE_A-Pad2)") (class "Default")
      (node (ref "U2") (pin "2") (pinfunction "~PHASE_A_2") (pintype "passive"))
    )
    (net (code "108") (name "unconnected-(U2-~PHASE_B-Pad21)") (class "Default")
      (node (ref "U2") (pin "21") (pinfunction "~PHASE_B_21") (pintype "passive"))
    )
    (net (code "109") (name "unconnected-(U3-ENABLE-Pad17)") (class "Default")
      (node (ref "U3") (pin "17") (pinfunction "ENABLE_17") (pintype "passive+no_connect"))
    )
    (net (code "110") (name "unconnected-(U3-FAULT_IN-Pad6)") (class "Default")
      (node (ref "U3") (pin "6") (pinfunction "FAULT_IN_6") (pintype "passive+no_connect"))
    )
    (net (code "111") (name "unconnected-(U3-HOLD_I_ADJ-Pad3)") (class "Default")
      (node (ref "U3") (pin "3") (pinfunction "HOLD_I_ADJ_3") (pintype "passive+no_connect"))
    )
    (net (code "112") (name "unconnected-(U3-I_REF-Pad4)") (class "Default")
      (node (ref "U3") (pin "4") (pinfunction "I_REF_4") (pintype "passive+no_connect"))
    )
    (net (code "113") (name "unconnected-(U3-PHASE_A-Pad1)") (class "Default")
      (node (ref "U3") (pin "1") (pinfunction "PHASE_A_1") (pintype "passive"))
    )
    (net (code "114") (name "unconnected-(U3-PHASE_B-Pad20)") (class "Default")
      (node (ref "U3") (pin "20") (pinfunction "PHASE_B_20") (pintype "passive"))
    )
    (net (code "115") (name "unconnected-(U3-~PHASE_A-Pad2)") (class "Default")
      (node (ref "U3") (pin "2") (pinfunction "~PHASE_A_2") (pintype "passive"))
    )
    (net (code "116") (name "unconnected-(U3-~PHASE_B-Pad21)") (class "Default")
      (node (ref "U3") (pin "21") (pinfunction "~PHASE_B_21") (pintype "passive"))
    )
    (net (code "117") (name "unconnected-(U4-4A1-Pad30)") (class "Default")
      (node (ref "U4") (pin "30") (pinfunction "4A1_30") (pintype "input+no_connect"))
    )
    (net (code "118") (name "unconnected-(U4-4Y1-Pad19)") (class "Default")
      (node (ref "U4") (pin "19") (pinfunction "4Y1_19") (pintype "tri_state+no_connect"))
    )
    (net (code "119") (name "unconnected-(U5-1A1-Pad47)") (class "Default")
      (node (ref "U5") (pin "47") (pinfunction "1A1_47") (pintype "input+no_connect"))
    )
    (net (code "120") (name "unconnected-(U5-1A2-Pad46)") (class "Default")
      (node (ref "U5") (pin "46") (pinfunction "1A2_46") (pintype "input+no_connect"))
    )
    (net (code "121") (name "unconnected-(U5-1A3-Pad44)") (class "Default")
      (node (ref "U5") (pin "44") (pinfunction "1A3_44") (pintype "input+no_connect"))
    )
    (net (code "122") (name "unconnected-(U5-1A4-Pad43)") (class "Default")
      (node (ref "U5") (pin "43") (pinfunction "1A4_43") (pintype "input+no_connect"))
    )
    (net (code "123") (name "unconnected-(U5-1Y1-Pad2)") (class "Default")
      (node (ref "U5") (pin "2") (pinfunction "1Y1_2") (pintype "tri_state+no_connect"))
    )
    (net (code "124") (name "unconnected-(U5-1Y2-Pad3)") (class "Default")
      (node (ref "U5") (pin "3") (pinfunction "1Y2_3") (pintype "tri_state+no_connect"))
    )
    (net (code "125") (name "unconnected-(U5-1Y3-Pad5)") (class "Default")
      (node (ref "U5") (pin "5") (pinfunction "1Y3_5") (pintype "tri_state+no_connect"))
    )
    (net (code "126") (name "unconnected-(U5-1Y4-Pad6)") (class "Default")
      (node (ref "U5") (pin "6") (pinfunction "1Y4_6") (pintype "tri_state+no_connect"))
    )
    (net (code "127") (name "unconnected-(U5-2A1-Pad41)") (class "Default")
      (node (ref "U5") (pin "41") (pinfunction "2A1_41") (pintype "input+no_connect"))
    )
    (net (code "128") (name "unconnected-(U5-2A2-Pad40)") (class "Default")
      (node (ref "U5") (pin "40") (pinfunction "2A2_40") (pintype "input+no_connect"))
    )
    (net (code "129") (name "unconnected-(U5-2A3-Pad38)") (class "Default")
      (node (ref "U5") (pin "38") (pinfunction "2A3_38") (pintype "input+no_connect"))
    )
    (net (code "130") (name "unconnected-(U5-2A4-Pad37)") (class "Default")
      (node (ref "U5") (pin "37") (pinfunction "2A4_37") (pintype "input+no_connect"))
    )
    (net (code "131") (name "unconnected-(U5-2Y1-Pad8)") (class "Default")
      (node (ref "U5") (pin "8") (pinfunction "2Y1_8") (pintype "tri_state+no_connect"))
    )
    (net (code "132") (name "unconnected-(U5-2Y2-Pad9)") (class "Default")
      (node (ref "U5") (pin "9") (pinfunction "2Y2_9") (pintype "tri_state+no_connect"))
    )
    (net (code "133") (name "unconnected-(U5-2Y3-Pad11)") (class "Default")
      (node (ref "U5") (pin "11") (pinfunction "2Y3_11") (pintype "tri_state+no_connect"))
    )
    (net (code "134") (name "unconnected-(U5-2Y4-Pad12)") (class "Default")
      (node (ref "U5") (pin "12") (pinfunction "2Y4_12") (pintype "tri_state+no_connect"))
    )
    (net (code "135") (name "unconnected-(U5-3A1-Pad36)") (class "Default")
      (node (ref "U5") (pin "36") (pinfunction "3A1_36") (pintype "input+no_connect"))
    )
    (net (code "136") (name "unconnected-(U5-3Y1-Pad13)") (class "Default")
      (node (ref "U5") (pin "13") (pinfunction "3Y1_13") (pintype "tri_state+no_connect"))
    )
    (net (code "137") (name "unconnected-(U5-4A4-Pad26)") (class "Default")
      (node (ref "U5") (pin "26") (pinfunction "4A4_26") (pintype "input+no_connect"))
    )
    (net (code "138") (name "unconnected-(U5-4Y4-Pad23)") (class "Default")
      (node (ref "U5") (pin "23") (pinfunction "4Y4_23") (pintype "tri_state+no_connect"))
    )
  )
)
